# SCH_Robot-Transporter_2025-06-01.net
KiCad netlist of a schematic drawn in EasyEDA
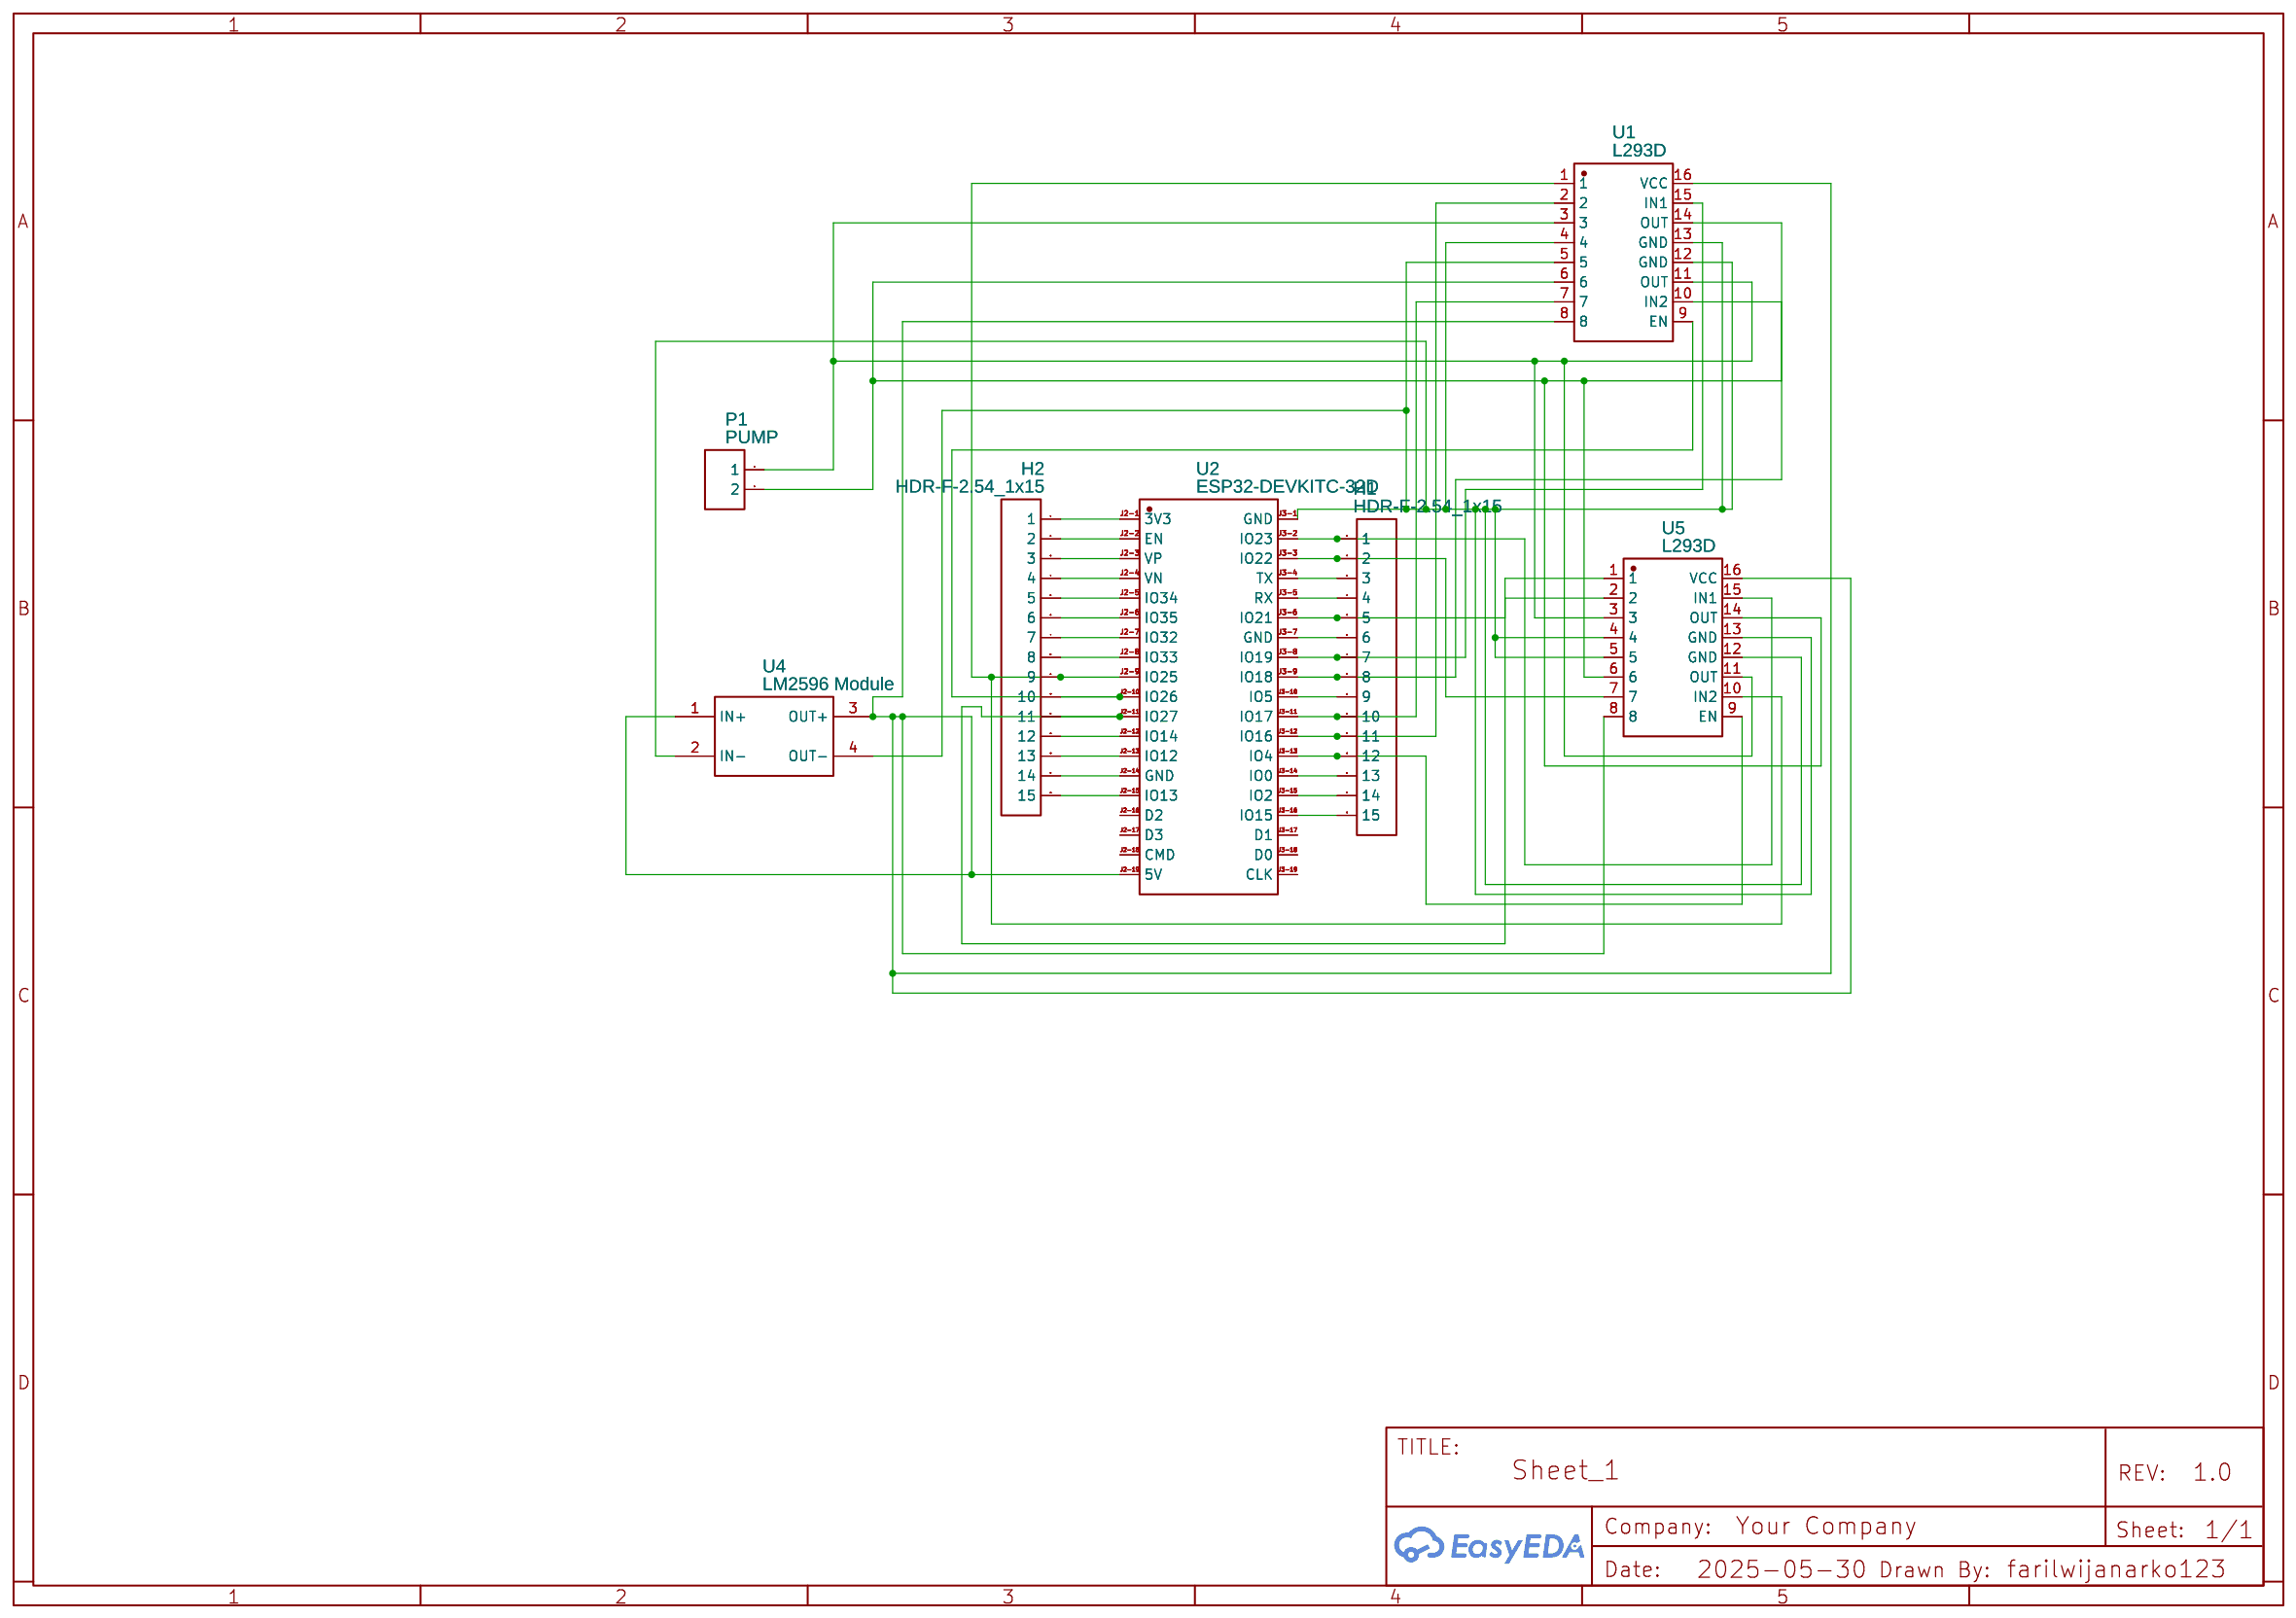
[diagram p0: schematic sheet]

(export (version "E")
  (design (tool "Eeschema 10.0.6"))
  (components
    (comp (ref "H1") (value "HDR-F-2.54_1x15") (libsource (lib "") (part "HDR-F-2.54_1x15")))
    (comp (ref "H2") (value "HDR-F-2.54_1x15") (libsource (lib "") (part "HDR-F-2.54_1x15_1")))
    (comp (ref "P1") (value "PUMP") (libsource (lib "") (part "CONN-TH_2P-P5.00")))
    (comp (ref "U1") (value "L293D") (libsource (lib "") (part "L293D")))
    (comp (ref "U2")
      (value "ESP32-DEVKITC-32D")
      (fields
        (field (name "Manufacturer Part") "ESP32-DevKitC-32D")
        (field (name "Manufacturer") "ESPRESSIF(乐鑫)")
      )
      (libsource (lib "") (part "ESP32-DEVKITC-32D"))
    )
    (comp (ref "U4") (value "LM2596 Module") (libsource (lib "") (part "LM2596 Module")))
    (comp (ref "U5") (value "L293D") (libsource (lib "") (part "L293D")))
  )
  (nets
    (net (code "1") (name "Net-(H1-Pad6)") (class "Default")
      (node (ref "H1") (pin "6") (pinfunction "6_6") (pintype "unspecified"))
      (node (ref "U2") (pin "J3-7") (pinfunction "GND_J3-7") (pintype "unspecified"))
    )
    (net (code "2") (name "Net-(H2-Pad14)") (class "Default")
      (node (ref "H2") (pin "14") (pinfunction "14_14") (pintype "unspecified"))
      (node (ref "U2") (pin "J2-14") (pinfunction "GND_J2-14") (pintype "unspecified"))
    )
    (net (code "3") (name "Net-(P1-Pad1)") (class "Default")
      (node (ref "P1") (pin "1") (pinfunction "1_1") (pintype "unspecified"))
      (node (ref "U1") (pin "11") (pinfunction "OUT_11") (pintype "unspecified"))
      (node (ref "U1") (pin "3") (pinfunction "3_3") (pintype "unspecified"))
      (node (ref "U5") (pin "11") (pinfunction "OUT_11") (pintype "unspecified"))
      (node (ref "U5") (pin "3") (pinfunction "3_3") (pintype "unspecified"))
    )
    (net (code "4") (name "Net-(P1-Pad2)") (class "Default")
      (node (ref "P1") (pin "2") (pinfunction "2_2") (pintype "unspecified"))
      (node (ref "U1") (pin "14") (pinfunction "OUT_14") (pintype "unspecified"))
      (node (ref "U1") (pin "6") (pinfunction "6_6") (pintype "unspecified"))
      (node (ref "U5") (pin "14") (pinfunction "OUT_14") (pintype "unspecified"))
      (node (ref "U5") (pin "6") (pinfunction "6_6") (pintype "unspecified"))
    )
    (net (code "5") (name "Net-(U1-EN)") (class "Default")
      (node (ref "H2") (pin "10") (pinfunction "10_10") (pintype "unspecified"))
      (node (ref "U1") (pin "9") (pinfunction "EN_9") (pintype "unspecified"))
      (node (ref "U2") (pin "J2-10") (pinfunction "IO26_J2-10") (pintype "unspecified"))
    )
    (net (code "6") (name "Net-(U1-IN1)") (class "Default")
      (node (ref "H1") (pin "7") (pinfunction "7_7") (pintype "unspecified"))
      (node (ref "U1") (pin "15") (pinfunction "IN1_15") (pintype "unspecified"))
      (node (ref "U2") (pin "J3-8") (pinfunction "IO19_J3-8") (pintype "unspecified"))
    )
    (net (code "7") (name "Net-(U1-IN2)") (class "Default")
      (node (ref "H1") (pin "8") (pinfunction "8_8") (pintype "unspecified"))
      (node (ref "U1") (pin "10") (pinfunction "IN2_10") (pintype "unspecified"))
      (node (ref "U2") (pin "J3-9") (pinfunction "IO18_J3-9") (pintype "unspecified"))
    )
    (net (code "8") (name "Net-(U1-VCC)") (class "Default")
      (node (ref "U1") (pin "16") (pinfunction "VCC_16") (pintype "unspecified"))
      (node (ref "U1") (pin "8") (pinfunction "8_8") (pintype "unspecified"))
      (node (ref "U2") (pin "J2-19") (pinfunction "5V_J2-19") (pintype "unspecified"))
      (node (ref "U4") (pin "1") (pinfunction "IN+_1") (pintype "unspecified"))
      (node (ref "U4") (pin "3") (pinfunction "OUT+_3") (pintype "unspecified"))
      (node (ref "U5") (pin "16") (pinfunction "VCC_16") (pintype "unspecified"))
      (node (ref "U5") (pin "8") (pinfunction "8_8") (pintype "unspecified"))
    )
    (net (code "9") (name "Net-(U2-3V3)") (class "Default")
      (node (ref "H2") (pin "1") (pinfunction "1_1") (pintype "unspecified"))
      (node (ref "U2") (pin "J2-1") (pinfunction "3V3_J2-1") (pintype "unspecified"))
    )
    (net (code "10") (name "Net-(U2-EN)") (class "Default")
      (node (ref "H2") (pin "2") (pinfunction "2_2") (pintype "unspecified"))
      (node (ref "U2") (pin "J2-2") (pinfunction "EN_J2-2") (pintype "unspecified"))
    )
    (net (code "11") (name "Net-(U2-IO0)") (class "Default")
      (node (ref "H1") (pin "13") (pinfunction "13_13") (pintype "unspecified"))
      (node (ref "U2") (pin "J3-14") (pinfunction "IO0_J3-14") (pintype "unspecified"))
    )
    (net (code "12") (name "Net-(U2-IO2)") (class "Default")
      (node (ref "H1") (pin "14") (pinfunction "14_14") (pintype "unspecified"))
      (node (ref "U2") (pin "J3-15") (pinfunction "IO2_J3-15") (pintype "unspecified"))
    )
    (net (code "13") (name "Net-(U2-IO4)") (class "Default")
      (node (ref "H1") (pin "12") (pinfunction "12_12") (pintype "unspecified"))
      (node (ref "U2") (pin "J3-13") (pinfunction "IO4_J3-13") (pintype "unspecified"))
      (node (ref "U5") (pin "9") (pinfunction "EN_9") (pintype "unspecified"))
    )
    (net (code "14") (name "Net-(U2-IO5)") (class "Default")
      (node (ref "H1") (pin "9") (pinfunction "9_9") (pintype "unspecified"))
      (node (ref "U2") (pin "J3-10") (pinfunction "IO5_J3-10") (pintype "unspecified"))
    )
    (net (code "15") (name "Net-(U2-IO12)") (class "Default")
      (node (ref "H2") (pin "13") (pinfunction "13_13") (pintype "unspecified"))
      (node (ref "U2") (pin "J2-13") (pinfunction "IO12_J2-13") (pintype "unspecified"))
    )
    (net (code "16") (name "Net-(U2-IO13)") (class "Default")
      (node (ref "H2") (pin "15") (pinfunction "15_15") (pintype "unspecified"))
      (node (ref "U2") (pin "J2-15") (pinfunction "IO13_J2-15") (pintype "unspecified"))
    )
    (net (code "17") (name "Net-(U2-IO14)") (class "Default")
      (node (ref "H2") (pin "12") (pinfunction "12_12") (pintype "unspecified"))
      (node (ref "U2") (pin "J2-12") (pinfunction "IO14_J2-12") (pintype "unspecified"))
    )
    (net (code "18") (name "Net-(U2-IO15)") (class "Default")
      (node (ref "H1") (pin "15") (pinfunction "15_15") (pintype "unspecified"))
      (node (ref "U2") (pin "J3-16") (pinfunction "IO15_J3-16") (pintype "unspecified"))
    )
    (net (code "19") (name "Net-(U2-IO16)") (class "Default")
      (node (ref "H1") (pin "11") (pinfunction "11_11") (pintype "unspecified"))
      (node (ref "U1") (pin "2") (pinfunction "2_2") (pintype "unspecified"))
      (node (ref "U2") (pin "J3-12") (pinfunction "IO16_J3-12") (pintype "unspecified"))
    )
    (net (code "20") (name "Net-(U2-IO17)") (class "Default")
      (node (ref "H1") (pin "10") (pinfunction "10_10") (pintype "unspecified"))
      (node (ref "U1") (pin "7") (pinfunction "7_7") (pintype "unspecified"))
      (node (ref "U2") (pin "J3-11") (pinfunction "IO17_J3-11") (pintype "unspecified"))
    )
    (net (code "21") (name "Net-(U2-IO21)") (class "Default")
      (node (ref "H1") (pin "5") (pinfunction "5_5") (pintype "unspecified"))
      (node (ref "U2") (pin "J3-6") (pinfunction "IO21_J3-6") (pintype "unspecified"))
      (node (ref "U5") (pin "2") (pinfunction "2_2") (pintype "unspecified"))
    )
    (net (code "22") (name "Net-(U2-IO22)") (class "Default")
      (node (ref "H1") (pin "2") (pinfunction "2_2") (pintype "unspecified"))
      (node (ref "U2") (pin "J3-3") (pinfunction "IO22_J3-3") (pintype "unspecified"))
      (node (ref "U5") (pin "7") (pinfunction "7_7") (pintype "unspecified"))
    )
    (net (code "23") (name "Net-(U2-IO23)") (class "Default")
      (node (ref "H1") (pin "1") (pinfunction "1_1") (pintype "unspecified"))
      (node (ref "U2") (pin "J3-2") (pinfunction "IO23_J3-2") (pintype "unspecified"))
      (node (ref "U5") (pin "15") (pinfunction "IN1_15") (pintype "unspecified"))
    )
    (net (code "24") (name "Net-(U2-IO25)") (class "Default")
      (node (ref "H2") (pin "9") (pinfunction "9_9") (pintype "unspecified"))
      (node (ref "U1") (pin "1") (pinfunction "1_1") (pintype "unspecified"))
      (node (ref "U2") (pin "J2-9") (pinfunction "IO25_J2-9") (pintype "unspecified"))
      (node (ref "U5") (pin "10") (pinfunction "IN2_10") (pintype "unspecified"))
    )
    (net (code "25") (name "Net-(U2-IO27)") (class "Default")
      (node (ref "H2") (pin "11") (pinfunction "11_11") (pintype "unspecified"))
      (node (ref "U2") (pin "J2-11") (pinfunction "IO27_J2-11") (pintype "unspecified"))
      (node (ref "U5") (pin "1") (pinfunction "1_1") (pintype "unspecified"))
    )
    (net (code "26") (name "Net-(U2-IO32)") (class "Default")
      (node (ref "H2") (pin "7") (pinfunction "7_7") (pintype "unspecified"))
      (node (ref "U2") (pin "J2-7") (pinfunction "IO32_J2-7") (pintype "unspecified"))
    )
    (net (code "27") (name "Net-(U2-IO33)") (class "Default")
      (node (ref "H2") (pin "8") (pinfunction "8_8") (pintype "unspecified"))
      (node (ref "U2") (pin "J2-8") (pinfunction "IO33_J2-8") (pintype "unspecified"))
    )
    (net (code "28") (name "Net-(U2-IO34)") (class "Default")
      (node (ref "H2") (pin "5") (pinfunction "5_5") (pintype "unspecified"))
      (node (ref "U2") (pin "J2-5") (pinfunction "IO34_J2-5") (pintype "unspecified"))
    )
    (net (code "29") (name "Net-(U2-IO35)") (class "Default")
      (node (ref "H2") (pin "6") (pinfunction "6_6") (pintype "unspecified"))
      (node (ref "U2") (pin "J2-6") (pinfunction "IO35_J2-6") (pintype "unspecified"))
    )
    (net (code "30") (name "Net-(U2-RX)") (class "Default")
      (node (ref "H1") (pin "4") (pinfunction "4_4") (pintype "unspecified"))
      (node (ref "U2") (pin "J3-5") (pinfunction "RX_J3-5") (pintype "unspecified"))
    )
    (net (code "31") (name "Net-(U2-TX)") (class "Default")
      (node (ref "H1") (pin "3") (pinfunction "3_3") (pintype "unspecified"))
      (node (ref "U2") (pin "J3-4") (pinfunction "TX_J3-4") (pintype "unspecified"))
    )
    (net (code "32") (name "Net-(U2-VN)") (class "Default")
      (node (ref "H2") (pin "4") (pinfunction "4_4") (pintype "unspecified"))
      (node (ref "U2") (pin "J2-4") (pinfunction "VN_J2-4") (pintype "unspecified"))
    )
    (net (code "33") (name "Net-(U2-VP)") (class "Default")
      (node (ref "H2") (pin "3") (pinfunction "3_3") (pintype "unspecified"))
      (node (ref "U2") (pin "J2-3") (pinfunction "VP_J2-3") (pintype "unspecified"))
    )
    (net (code "34") (name "Net-(U4-IN-)") (class "Default")
      (node (ref "U1") (pin "12") (pinfunction "GND_12") (pintype "unspecified"))
      (node (ref "U1") (pin "13") (pinfunction "GND_13") (pintype "unspecified"))
      (node (ref "U1") (pin "4") (pinfunction "4_4") (pintype "unspecified"))
      (node (ref "U1") (pin "5") (pinfunction "5_5") (pintype "unspecified"))
      (node (ref "U2") (pin "J3-1") (pinfunction "GND_J3-1") (pintype "unspecified"))
      (node (ref "U4") (pin "2") (pinfunction "IN-_2") (pintype "unspecified"))
      (node (ref "U4") (pin "4") (pinfunction "OUT-_4") (pintype "unspecified"))
      (node (ref "U5") (pin "12") (pinfunction "GND_12") (pintype "unspecified"))
      (node (ref "U5") (pin "13") (pinfunction "GND_13") (pintype "unspecified"))
      (node (ref "U5") (pin "4") (pinfunction "4_4") (pintype "unspecified"))
      (node (ref "U5") (pin "5") (pinfunction "5_5") (pintype "unspecified"))
    )
    (net (code "35") (name "unconnected-(U2-CLK-PadJ3-19)") (class "Default")
      (node (ref "U2") (pin "J3-19") (pinfunction "CLK_J3-19") (pintype "unspecified"))
    )
    (net (code "36") (name "unconnected-(U2-CMD-PadJ2-18)") (class "Default")
      (node (ref "U2") (pin "J2-18") (pinfunction "CMD_J2-18") (pintype "unspecified"))
    )
    (net (code "37") (name "unconnected-(U2-D0-PadJ3-18)") (class "Default")
      (node (ref "U2") (pin "J3-18") (pinfunction "D0_J3-18") (pintype "unspecified"))
    )
    (net (code "38") (name "unconnected-(U2-D1-PadJ3-17)") (class "Default")
      (node (ref "U2") (pin "J3-17") (pinfunction "D1_J3-17") (pintype "unspecified"))
    )
    (net (code "39") (name "unconnected-(U2-D2-PadJ2-16)") (class "Default")
      (node (ref "U2") (pin "J2-16") (pinfunction "D2_J2-16") (pintype "unspecified"))
    )
    (net (code "40") (name "unconnected-(U2-D3-PadJ2-17)") (class "Default")
      (node (ref "U2") (pin "J2-17") (pinfunction "D3_J2-17") (pintype "unspecified"))
    )
  )
)
